# sms_adapter.net
KiCad netlist of a schematic drawn in EAGLE
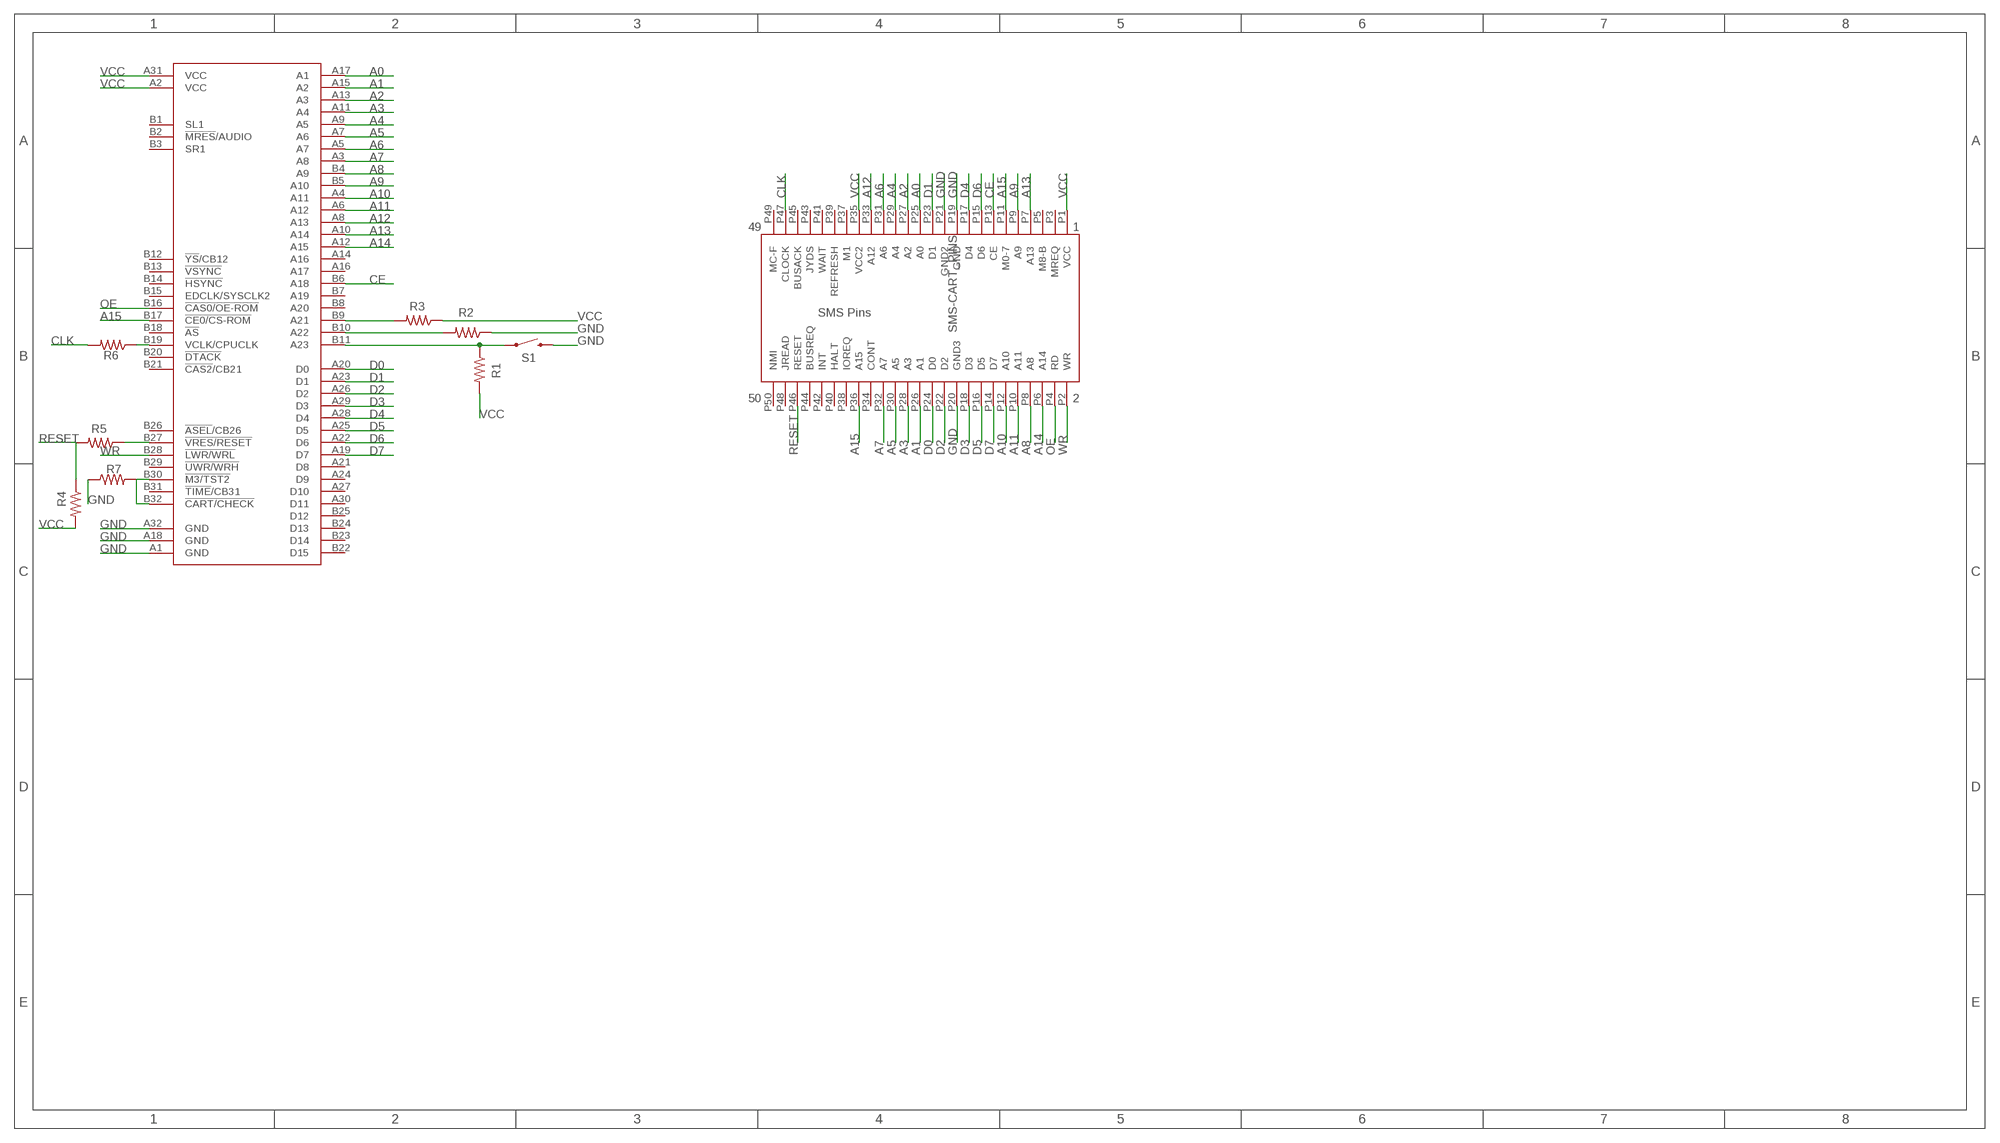
[diagram p0: schematic, sheet 1]

(export (version "E")
  (design (tool "Eeschema 10.0.6"))
  (components
    (comp (ref "CN3")
      (value "MEGADRIVE-CART-CONNECTOR-ORDERED")
      (footprint "eagle-import:MEGADRIVE-CART-CONNECTOR")
      (libsource (lib "eagle-import") (part "MEGADRIVE-CART-CONNECTOR-ORDERED"))
    )
    (comp (ref "R1")
      (value "56K")
      (footprint "eagle-import:M1206")
      (libsource (lib "eagle-import") (part "R-US_M1206"))
    )
    (comp (ref "R2")
      (value "0")
      (footprint "eagle-import:M1206")
      (libsource (lib "eagle-import") (part "R-US_M1206"))
    )
    (comp (ref "R3")
      (value "0")
      (footprint "eagle-import:M1206")
      (libsource (lib "eagle-import") (part "R-US_M1206"))
    )
    (comp (ref "R4")
      (value "0")
      (footprint "eagle-import:M1206")
      (libsource (lib "eagle-import") (part "R-US_M1206"))
    )
    (comp (ref "R5")
      (value "NP")
      (footprint "eagle-import:M1206")
      (libsource (lib "eagle-import") (part "R-US_M1206"))
    )
    (comp (ref "R6")
      (value "NP")
      (footprint "eagle-import:M1206")
      (libsource (lib "eagle-import") (part "R-US_M1206"))
    )
    (comp (ref "R7")
      (value "0")
      (footprint "eagle-import:M1206")
      (libsource (lib "eagle-import") (part "R-US_M1206"))
    )
    (comp (ref "S1")
      (value "MOMENTARY-SWITCH-SPST-SMD-5.2MM")
      (footprint "eagle-import:TACTILE_SWITCH_SMD_5.2MM")
      (libsource (lib "eagle-import") (part "MOMENTARY-SWITCH-SPST-SMD-5.2MM"))
    )
    (comp (ref "U$1")
      (value "SMS-CART_PINS")
      (footprint "eagle-import:SMS_PINS")
      (libsource (lib "eagle-import") (part "SMS-CART_PINS"))
    )
  )
  (nets
    (net (code "1") (name "/A0") (class "Default")
      (node (ref "CN3") (pin "A17") (pinfunction "A1_A17") (pintype "bidirectional"))
      (node (ref "U$1") (pin "P25") (pinfunction "A0_P25") (pintype "bidirectional"))
    )
    (net (code "2") (name "/A1") (class "Default")
      (node (ref "CN3") (pin "A15") (pinfunction "A2_A15") (pintype "bidirectional"))
      (node (ref "U$1") (pin "P26") (pinfunction "A1_P26") (pintype "bidirectional"))
    )
    (net (code "3") (name "/A2") (class "Default")
      (node (ref "CN3") (pin "A13") (pinfunction "A3_A13") (pintype "bidirectional"))
      (node (ref "U$1") (pin "P27") (pinfunction "A2_P27") (pintype "bidirectional"))
    )
    (net (code "4") (name "/A3") (class "Default")
      (node (ref "CN3") (pin "A11") (pinfunction "A4_A11") (pintype "bidirectional"))
      (node (ref "U$1") (pin "P28") (pinfunction "A3_P28") (pintype "bidirectional"))
    )
    (net (code "5") (name "/A4") (class "Default")
      (node (ref "CN3") (pin "A9") (pinfunction "A5_A9") (pintype "bidirectional"))
      (node (ref "U$1") (pin "P29") (pinfunction "A4_P29") (pintype "bidirectional"))
    )
    (net (code "6") (name "/A5") (class "Default")
      (node (ref "CN3") (pin "A7") (pinfunction "A6_A7") (pintype "bidirectional"))
      (node (ref "U$1") (pin "P30") (pinfunction "A5_P30") (pintype "bidirectional"))
    )
    (net (code "7") (name "/A6") (class "Default")
      (node (ref "CN3") (pin "A5") (pinfunction "A7_A5") (pintype "bidirectional"))
      (node (ref "U$1") (pin "P31") (pinfunction "A6_P31") (pintype "bidirectional"))
    )
    (net (code "8") (name "/A7") (class "Default")
      (node (ref "CN3") (pin "A3") (pinfunction "A8_A3") (pintype "bidirectional"))
      (node (ref "U$1") (pin "P32") (pinfunction "A7_P32") (pintype "bidirectional"))
    )
    (net (code "9") (name "/A8") (class "Default")
      (node (ref "CN3") (pin "B4") (pinfunction "A9_B4") (pintype "bidirectional"))
      (node (ref "U$1") (pin "P8") (pinfunction "A8_P8") (pintype "bidirectional"))
    )
    (net (code "10") (name "/A9") (class "Default")
      (node (ref "CN3") (pin "B5") (pinfunction "A10_B5") (pintype "bidirectional"))
      (node (ref "U$1") (pin "P9") (pinfunction "A9_P9") (pintype "bidirectional"))
    )
    (net (code "11") (name "/A10") (class "Default")
      (node (ref "CN3") (pin "A4") (pinfunction "A11_A4") (pintype "bidirectional"))
      (node (ref "U$1") (pin "P12") (pinfunction "A10_P12") (pintype "bidirectional"))
    )
    (net (code "12") (name "/A11") (class "Default")
      (node (ref "CN3") (pin "A6") (pinfunction "A12_A6") (pintype "bidirectional"))
      (node (ref "U$1") (pin "P10") (pinfunction "A11_P10") (pintype "bidirectional"))
    )
    (net (code "13") (name "/A12") (class "Default")
      (node (ref "CN3") (pin "A8") (pinfunction "A13_A8") (pintype "bidirectional"))
      (node (ref "U$1") (pin "P33") (pinfunction "A12_P33") (pintype "bidirectional"))
    )
    (net (code "14") (name "/A13") (class "Default")
      (node (ref "CN3") (pin "A10") (pinfunction "A14_A10") (pintype "bidirectional"))
      (node (ref "U$1") (pin "P7") (pinfunction "A13_P7") (pintype "bidirectional"))
    )
    (net (code "15") (name "/A14") (class "Default")
      (node (ref "CN3") (pin "A12") (pinfunction "A15_A12") (pintype "bidirectional"))
      (node (ref "U$1") (pin "P6") (pinfunction "A14_P6") (pintype "bidirectional"))
    )
    (net (code "16") (name "/A15") (class "Default")
      (node (ref "CN3") (pin "B17") (pinfunction "~{CE0/CS-ROM}_B17") (pintype "bidirectional"))
      (node (ref "U$1") (pin "P11") (pinfunction "M0-7_P11") (pintype "bidirectional"))
      (node (ref "U$1") (pin "P36") (pinfunction "A15_P36") (pintype "bidirectional"))
    )
    (net (code "17") (name "/CE") (class "Default")
      (node (ref "CN3") (pin "B6") (pinfunction "A18_B6") (pintype "bidirectional"))
      (node (ref "U$1") (pin "P13") (pinfunction "CE_P13") (pintype "bidirectional"))
    )
    (net (code "18") (name "/CLK") (class "Default")
      (node (ref "R6") (pin "2") (pinfunction "2_2") (pintype "passive"))
      (node (ref "U$1") (pin "P47") (pinfunction "CLOCK_P47") (pintype "bidirectional"))
    )
    (net (code "19") (name "/D0") (class "Default")
      (node (ref "CN3") (pin "A20") (pinfunction "D0_A20") (pintype "bidirectional"))
      (node (ref "U$1") (pin "P24") (pinfunction "D0_P24") (pintype "bidirectional"))
    )
    (net (code "20") (name "/D1") (class "Default")
      (node (ref "CN3") (pin "A23") (pinfunction "D1_A23") (pintype "bidirectional"))
      (node (ref "U$1") (pin "P23") (pinfunction "D1_P23") (pintype "bidirectional"))
    )
    (net (code "21") (name "/D2") (class "Default")
      (node (ref "CN3") (pin "A26") (pinfunction "D2_A26") (pintype "bidirectional"))
      (node (ref "U$1") (pin "P22") (pinfunction "D2_P22") (pintype "bidirectional"))
    )
    (net (code "22") (name "/D3") (class "Default")
      (node (ref "CN3") (pin "A29") (pinfunction "D3_A29") (pintype "bidirectional"))
      (node (ref "U$1") (pin "P18") (pinfunction "D3_P18") (pintype "bidirectional"))
    )
    (net (code "23") (name "/D4") (class "Default")
      (node (ref "CN3") (pin "A28") (pinfunction "D4_A28") (pintype "bidirectional"))
      (node (ref "U$1") (pin "P17") (pinfunction "D4_P17") (pintype "bidirectional"))
    )
    (net (code "24") (name "/D5") (class "Default")
      (node (ref "CN3") (pin "A25") (pinfunction "D5_A25") (pintype "bidirectional"))
      (node (ref "U$1") (pin "P16") (pinfunction "D5_P16") (pintype "bidirectional"))
    )
    (net (code "25") (name "/D6") (class "Default")
      (node (ref "CN3") (pin "A22") (pinfunction "D6_A22") (pintype "bidirectional"))
      (node (ref "U$1") (pin "P15") (pinfunction "D6_P15") (pintype "bidirectional"))
    )
    (net (code "26") (name "/D7") (class "Default")
      (node (ref "CN3") (pin "A19") (pinfunction "D7_A19") (pintype "bidirectional"))
      (node (ref "U$1") (pin "P14") (pinfunction "D7_P14") (pintype "bidirectional"))
    )
    (net (code "27") (name "/GND") (class "Default")
      (node (ref "CN3") (pin "A1") (pinfunction "GND_A1") (pintype "bidirectional"))
      (node (ref "CN3") (pin "A18") (pinfunction "GND_A18") (pintype "bidirectional"))
      (node (ref "CN3") (pin "A32") (pinfunction "GND_A32") (pintype "bidirectional"))
      (node (ref "R2") (pin "1") (pinfunction "1_1") (pintype "passive"))
      (node (ref "R7") (pin "1") (pinfunction "1_1") (pintype "passive"))
      (node (ref "S1") (pin "3") (pinfunction "2_3") (pintype "passive"))
      (node (ref "U$1") (pin "P19") (pinfunction "GND_P19") (pintype "bidirectional"))
      (node (ref "U$1") (pin "P20") (pinfunction "GND3_P20") (pintype "bidirectional"))
      (node (ref "U$1") (pin "P21") (pinfunction "GND2_P21") (pintype "bidirectional"))
    )
    (net (code "28") (name "/OE") (class "Default")
      (node (ref "CN3") (pin "B16") (pinfunction "~{CAS0/OE-ROM}_B16") (pintype "bidirectional"))
      (node (ref "U$1") (pin "P4") (pinfunction "RD_P4") (pintype "bidirectional"))
    )
    (net (code "29") (name "/RESET") (class "Default")
      (node (ref "R4") (pin "1") (pinfunction "1_1") (pintype "passive"))
      (node (ref "R5") (pin "2") (pinfunction "2_2") (pintype "passive"))
      (node (ref "U$1") (pin "P46") (pinfunction "RESET_P46") (pintype "bidirectional"))
    )
    (net (code "30") (name "/VCC") (class "Default")
      (node (ref "CN3") (pin "A2") (pinfunction "VCC_A2") (pintype "bidirectional"))
      (node (ref "CN3") (pin "A31") (pinfunction "VCC_A31") (pintype "bidirectional"))
      (node (ref "R1") (pin "2") (pinfunction "2_2") (pintype "passive"))
      (node (ref "R3") (pin "1") (pinfunction "1_1") (pintype "passive"))
      (node (ref "R4") (pin "2") (pinfunction "2_2") (pintype "passive"))
      (node (ref "U$1") (pin "P1") (pinfunction "VCC_P1") (pintype "bidirectional"))
      (node (ref "U$1") (pin "P35") (pinfunction "VCC2_P35") (pintype "bidirectional"))
    )
    (net (code "31") (name "/WR") (class "Default")
      (node (ref "CN3") (pin "B28") (pinfunction "~{LWR/WRL}_B28") (pintype "bidirectional"))
      (node (ref "U$1") (pin "P2") (pinfunction "WR_P2") (pintype "bidirectional"))
    )
    (net (code "32") (name "Net-(CN3-A21)") (class "Default")
      (node (ref "CN3") (pin "B9") (pinfunction "A21_B9") (pintype "bidirectional"))
      (node (ref "R3") (pin "2") (pinfunction "2_2") (pintype "passive"))
    )
    (net (code "33") (name "Net-(CN3-A22)") (class "Default")
      (node (ref "CN3") (pin "B10") (pinfunction "A22_B10") (pintype "bidirectional"))
      (node (ref "R2") (pin "2") (pinfunction "2_2") (pintype "passive"))
    )
    (net (code "34") (name "Net-(CN3-A23)") (class "Default")
      (node (ref "CN3") (pin "B11") (pinfunction "A23_B11") (pintype "bidirectional"))
      (node (ref "R1") (pin "1") (pinfunction "1_1") (pintype "passive"))
      (node (ref "S1") (pin "1") (pinfunction "1_1") (pintype "passive"))
    )
    (net (code "35") (name "Net-(CN3-VCLK{slash}CPUCLK)") (class "Default")
      (node (ref "CN3") (pin "B19") (pinfunction "VCLK/CPUCLK_B19") (pintype "bidirectional"))
      (node (ref "R6") (pin "1") (pinfunction "1_1") (pintype "passive"))
    )
    (net (code "36") (name "Net-(CN3-~{CART{slash}CHECK})") (class "Default")
      (node (ref "CN3") (pin "B30") (pinfunction "~{M3/TST2}_B30") (pintype "bidirectional"))
      (node (ref "CN3") (pin "B32") (pinfunction "~{CART/CHECK}_B32") (pintype "bidirectional"))
      (node (ref "R7") (pin "2") (pinfunction "2_2") (pintype "passive"))
    )
    (net (code "37") (name "Net-(CN3-~{VRES{slash}RESET})") (class "Default")
      (node (ref "CN3") (pin "B27") (pinfunction "~{VRES/RESET}_B27") (pintype "bidirectional"))
      (node (ref "R5") (pin "1") (pinfunction "1_1") (pintype "passive"))
    )
    (net (code "38") (name "unconnected-(CN3-A16-PadA14)") (class "Default")
      (node (ref "CN3") (pin "A14") (pinfunction "A16_A14") (pintype "bidirectional"))
    )
    (net (code "39") (name "unconnected-(CN3-A17-PadA16)") (class "Default")
      (node (ref "CN3") (pin "A16") (pinfunction "A17_A16") (pintype "bidirectional"))
    )
    (net (code "40") (name "unconnected-(CN3-A19-PadB7)") (class "Default")
      (node (ref "CN3") (pin "B7") (pinfunction "A19_B7") (pintype "bidirectional"))
    )
    (net (code "41") (name "unconnected-(CN3-A20-PadB8)") (class "Default")
      (node (ref "CN3") (pin "B8") (pinfunction "A20_B8") (pintype "bidirectional"))
    )
    (net (code "42") (name "unconnected-(CN3-D8-PadA21)") (class "Default")
      (node (ref "CN3") (pin "A21") (pinfunction "D8_A21") (pintype "bidirectional"))
    )
    (net (code "43") (name "unconnected-(CN3-D9-PadA24)") (class "Default")
      (node (ref "CN3") (pin "A24") (pinfunction "D9_A24") (pintype "bidirectional"))
    )
    (net (code "44") (name "unconnected-(CN3-D10-PadA27)") (class "Default")
      (node (ref "CN3") (pin "A27") (pinfunction "D10_A27") (pintype "bidirectional"))
    )
    (net (code "45") (name "unconnected-(CN3-D11-PadA30)") (class "Default")
      (node (ref "CN3") (pin "A30") (pinfunction "D11_A30") (pintype "bidirectional"))
    )
    (net (code "46") (name "unconnected-(CN3-D12-PadB25)") (class "Default")
      (node (ref "CN3") (pin "B25") (pinfunction "D12_B25") (pintype "bidirectional"))
    )
    (net (code "47") (name "unconnected-(CN3-D13-PadB24)") (class "Default")
      (node (ref "CN3") (pin "B24") (pinfunction "D13_B24") (pintype "bidirectional"))
    )
    (net (code "48") (name "unconnected-(CN3-D14-PadB23)") (class "Default")
      (node (ref "CN3") (pin "B23") (pinfunction "D14_B23") (pintype "bidirectional"))
    )
    (net (code "49") (name "unconnected-(CN3-D15-PadB22)") (class "Default")
      (node (ref "CN3") (pin "B22") (pinfunction "D15_B22") (pintype "bidirectional"))
    )
    (net (code "50") (name "unconnected-(CN3-EDCLK{slash}SYSCLK2-PadB15)") (class "Default")
      (node (ref "CN3") (pin "B15") (pinfunction "EDCLK/SYSCLK2_B15") (pintype "bidirectional"))
    )
    (net (code "51") (name "unconnected-(CN3-SL1-PadB1)") (class "Default")
      (node (ref "CN3") (pin "B1") (pinfunction "SL1_B1") (pintype "bidirectional"))
    )
    (net (code "52") (name "unconnected-(CN3-SR1-PadB3)") (class "Default")
      (node (ref "CN3") (pin "B3") (pinfunction "SR1_B3") (pintype "bidirectional"))
    )
    (net (code "53") (name "unconnected-(CN3-~{ASEL}{slash}CB26-PadB26)") (class "Default")
      (node (ref "CN3") (pin "B26") (pinfunction "~{ASEL}/CB26_B26") (pintype "bidirectional"))
    )
    (net (code "54") (name "unconnected-(CN3-~{AS}-PadB18)") (class "Default")
      (node (ref "CN3") (pin "B18") (pinfunction "~{AS}_B18") (pintype "bidirectional"))
    )
    (net (code "55") (name "unconnected-(CN3-~{CAS2}{slash}CB21-PadB21)") (class "Default")
      (node (ref "CN3") (pin "B21") (pinfunction "~{CAS2}/CB21_B21") (pintype "bidirectional"))
    )
    (net (code "56") (name "unconnected-(CN3-~{DTACK}-PadB20)") (class "Default")
      (node (ref "CN3") (pin "B20") (pinfunction "~{DTACK}_B20") (pintype "bidirectional"))
    )
    (net (code "57") (name "unconnected-(CN3-~{HSYNC}-PadB14)") (class "Default")
      (node (ref "CN3") (pin "B14") (pinfunction "~{HSYNC}_B14") (pintype "bidirectional"))
    )
    (net (code "58") (name "unconnected-(CN3-~{MRES}{slash}AUDIO-PadB2)") (class "Default")
      (node (ref "CN3") (pin "B2") (pinfunction "~{MRES}/AUDIO_B2") (pintype "bidirectional"))
    )
    (net (code "59") (name "unconnected-(CN3-~{TIME}{slash}CB31-PadB31)") (class "Default")
      (node (ref "CN3") (pin "B31") (pinfunction "~{TIME}/CB31_B31") (pintype "bidirectional"))
    )
    (net (code "60") (name "unconnected-(CN3-~{UWR{slash}WRH}-PadB29)") (class "Default")
      (node (ref "CN3") (pin "B29") (pinfunction "~{UWR/WRH}_B29") (pintype "bidirectional"))
    )
    (net (code "61") (name "unconnected-(CN3-~{VSYNC}-PadB13)") (class "Default")
      (node (ref "CN3") (pin "B13") (pinfunction "~{VSYNC}_B13") (pintype "bidirectional"))
    )
    (net (code "62") (name "unconnected-(CN3-~{YS}{slash}CB12-PadB12)") (class "Default")
      (node (ref "CN3") (pin "B12") (pinfunction "~{YS}/CB12_B12") (pintype "bidirectional"))
    )
    (net (code "63") (name "unconnected-(U$1-BUSACK-PadP45)") (class "Default")
      (node (ref "U$1") (pin "P45") (pinfunction "BUSACK_P45") (pintype "bidirectional"))
    )
    (net (code "64") (name "unconnected-(U$1-BUSREQ-PadP44)") (class "Default")
      (node (ref "U$1") (pin "P44") (pinfunction "BUSREQ_P44") (pintype "bidirectional"))
    )
    (net (code "65") (name "unconnected-(U$1-CONT-PadP34)") (class "Default")
      (node (ref "U$1") (pin "P34") (pinfunction "CONT_P34") (pintype "bidirectional"))
    )
    (net (code "66") (name "unconnected-(U$1-HALT-PadP40)") (class "Default")
      (node (ref "U$1") (pin "P40") (pinfunction "HALT_P40") (pintype "bidirectional"))
    )
    (net (code "67") (name "unconnected-(U$1-INT-PadP42)") (class "Default")
      (node (ref "U$1") (pin "P42") (pinfunction "INT_P42") (pintype "bidirectional"))
    )
    (net (code "68") (name "unconnected-(U$1-IOREQ-PadP38)") (class "Default")
      (node (ref "U$1") (pin "P38") (pinfunction "IOREQ_P38") (pintype "bidirectional"))
    )
    (net (code "69") (name "unconnected-(U$1-JREAD-PadP48)") (class "Default")
      (node (ref "U$1") (pin "P48") (pinfunction "JREAD_P48") (pintype "bidirectional"))
    )
    (net (code "70") (name "unconnected-(U$1-JYDS-PadP43)") (class "Default")
      (node (ref "U$1") (pin "P43") (pinfunction "JYDS_P43") (pintype "bidirectional"))
    )
    (net (code "71") (name "unconnected-(U$1-M1-PadP37)") (class "Default")
      (node (ref "U$1") (pin "P37") (pinfunction "M1_P37") (pintype "bidirectional"))
    )
    (net (code "72") (name "unconnected-(U$1-M8-B-PadP5)") (class "Default")
      (node (ref "U$1") (pin "P5") (pinfunction "M8-B_P5") (pintype "bidirectional"))
    )
    (net (code "73") (name "unconnected-(U$1-MC-F-PadP49)") (class "Default")
      (node (ref "U$1") (pin "P49") (pinfunction "MC-F_P49") (pintype "bidirectional"))
    )
    (net (code "74") (name "unconnected-(U$1-MREQ-PadP3)") (class "Default")
      (node (ref "U$1") (pin "P3") (pinfunction "MREQ_P3") (pintype "bidirectional"))
    )
    (net (code "75") (name "unconnected-(U$1-NMI-PadP50)") (class "Default")
      (node (ref "U$1") (pin "P50") (pinfunction "NMI_P50") (pintype "bidirectional"))
    )
    (net (code "76") (name "unconnected-(U$1-REFRESH-PadP39)") (class "Default")
      (node (ref "U$1") (pin "P39") (pinfunction "REFRESH_P39") (pintype "bidirectional"))
    )
    (net (code "77") (name "unconnected-(U$1-WAIT-PadP41)") (class "Default")
      (node (ref "U$1") (pin "P41") (pinfunction "WAIT_P41") (pintype "bidirectional"))
    )
  )
)
